# 03_External_Storage_Interface.net
KiCad netlist of a schematic drawn in Altium Designer
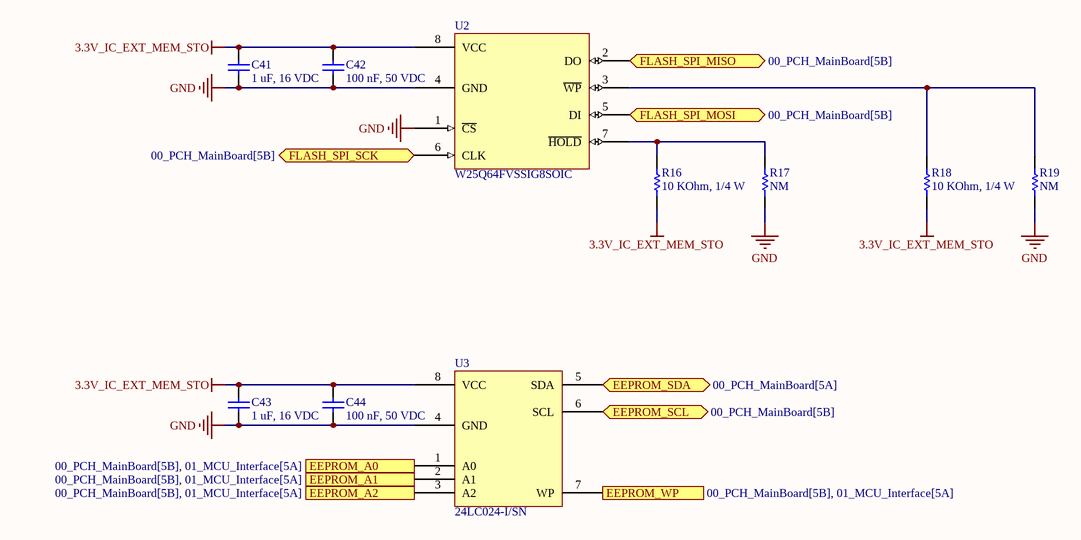
[diagram p0: 03_External_Storage_Interface.SchDoc]

(export (version "E")
  (design (tool "Eeschema 10.0.6"))
  (components
    (comp (ref "C41")
      (value "1 uF, 16 VDC")
      (footprint "CAP_0603")
      (description "CAP, size 0603, 1 uF, 16 VDC")
      (fields (field (name "TOLERANCE") "+/-10%"))
      (libsource (lib "Altium_Ceramic_Cap") (part "0106031051016"))
    )
    (comp (ref "C42")
      (value "100 nF, 50 VDC")
      (footprint "CAP_0603")
      (description "CAP, size 0603, 100 nF, 50 VDC")
      (fields (field (name "TOLERANCE") "+/-10%"))
      (libsource (lib "Altium_Ceramic_Cap") (part "0106031041050"))
    )
    (comp (ref "C43")
      (value "1 uF, 16 VDC")
      (footprint "CAP_0603")
      (description "CAP, size 0603, 1 uF, 16 VDC")
      (fields (field (name "TOLERANCE") "+/-10%"))
      (libsource (lib "Altium_Ceramic_Cap") (part "0106031051016"))
    )
    (comp (ref "C44")
      (value "100 nF, 50 VDC")
      (footprint "CAP_0603")
      (description "CAP, size 0603, 100 nF, 50 VDC")
      (fields (field (name "TOLERANCE") "+/-10%"))
      (libsource (lib "Altium_Ceramic_Cap") (part "0106031041050"))
    )
    (comp (ref "R16")
      (value "10 KOhm, 1/4 W")
      (footprint "resistor_0603")
      (description "RES, size 0603, 10 KOhm, 1/4 W")
      (libsource (lib "Altium_Resistor") (part "0006031031"))
    )
    (comp (ref "R17")
      (value "NM")
      (footprint "resistor_0603")
      (description "RES, size 0603, NM")
      (libsource (lib "Altium_Resistor") (part "000603_NM"))
    )
    (comp (ref "R18")
      (value "10 KOhm, 1/4 W")
      (footprint "resistor_0603")
      (description "RES, size 0603, 10 KOhm, 1/4 W")
      (libsource (lib "Altium_Resistor") (part "0006031031"))
    )
    (comp (ref "R19")
      (value "NM")
      (footprint "resistor_0603")
      (description "RES, size 0603, NM")
      (libsource (lib "Altium_Resistor") (part "000603_NM"))
    )
    (comp (ref "U2")
      (value "W25Q64FVSSIG8SOIC")
      (footprint "W25Qxx8SOIC")
      (description "IC FLASH 64MBIT SPI/QUAD 8SOIC")
      (fields (field (name "MANUFACTURER") "Winbond Electronics"))
      (libsource (lib "Altium_IC") (part "W25Q64FVSSIG8SOIC"))
    )
    (comp (ref "U3")
      (value "24LC024-I/SN")
      (footprint "24LCxxx-I/SN")
      (description "2 Kbit Electrically Erasable PROM")
      (fields (field (name "MANUFACTURER") "Microchip"))
      (libsource (lib "Altium_IC") (part "24LC024-I/SN"))
    )
  )
  (nets
    (net (code "1") (name "/EEPROM_A0") (class "Default")
      (node (ref "U3") (pin "1") (pinfunction "A0_1") (pintype "passive"))
    )
    (net (code "2") (name "/EEPROM_A1") (class "Default")
      (node (ref "U3") (pin "2") (pinfunction "A1_2") (pintype "passive"))
    )
    (net (code "3") (name "/EEPROM_A2") (class "Default")
      (node (ref "U3") (pin "3") (pinfunction "A2_3") (pintype "passive"))
    )
    (net (code "4") (name "/EEPROM_SCL") (class "Default")
      (node (ref "U3") (pin "6") (pinfunction "SCL_6") (pintype "passive"))
    )
    (net (code "5") (name "/EEPROM_SDA") (class "Default")
      (node (ref "U3") (pin "5") (pinfunction "SDA_5") (pintype "passive"))
    )
    (net (code "6") (name "/EEPROM_WP") (class "Default")
      (node (ref "U3") (pin "7") (pinfunction "WP_7") (pintype "passive"))
    )
    (net (code "7") (name "/FLASH_SPI_MISO") (class "Default")
      (node (ref "U2") (pin "2") (pinfunction "DO_2") (pintype "bidirectional"))
    )
    (net (code "8") (name "/FLASH_SPI_MOSI") (class "Default")
      (node (ref "U2") (pin "5") (pinfunction "DI_5") (pintype "bidirectional"))
    )
    (net (code "9") (name "/FLASH_SPI_SCK") (class "Default")
      (node (ref "U2") (pin "6") (pinfunction "CLK_6") (pintype "input"))
    )
    (net (code "10") (name "3.3V_IC_EXT_MEM_STO") (class "Default")
      (node (ref "C41") (pin "2") (pinfunction "2_2") (pintype "passive"))
      (node (ref "C42") (pin "2") (pinfunction "2_2") (pintype "passive"))
      (node (ref "C43") (pin "2") (pinfunction "2_2") (pintype "passive"))
      (node (ref "C44") (pin "2") (pinfunction "2_2") (pintype "passive"))
      (node (ref "R16") (pin "1") (pinfunction "1_1") (pintype "passive"))
      (node (ref "R18") (pin "1") (pinfunction "1_1") (pintype "passive"))
      (node (ref "U2") (pin "8") (pinfunction "VCC_8") (pintype "power_in"))
      (node (ref "U3") (pin "8") (pinfunction "VCC_8") (pintype "passive"))
    )
    (net (code "11") (name "GND") (class "Default")
      (node (ref "C41") (pin "1") (pinfunction "1_1") (pintype "passive"))
      (node (ref "C42") (pin "1") (pinfunction "1_1") (pintype "passive"))
      (node (ref "C43") (pin "1") (pinfunction "1_1") (pintype "passive"))
      (node (ref "C44") (pin "1") (pinfunction "1_1") (pintype "passive"))
      (node (ref "R17") (pin "1") (pinfunction "1_1") (pintype "passive"))
      (node (ref "R19") (pin "1") (pinfunction "1_1") (pintype "passive"))
      (node (ref "U2") (pin "1") (pinfunction "~{CS}_1") (pintype "input"))
      (node (ref "U2") (pin "4") (pinfunction "GND_4") (pintype "power_in"))
      (node (ref "U3") (pin "4") (pinfunction "GND_4") (pintype "passive"))
    )
    (net (code "12") (name "Net-(U2-~{HOLD})") (class "Default")
      (node (ref "R16") (pin "2") (pinfunction "2_2") (pintype "passive"))
      (node (ref "R17") (pin "2") (pinfunction "2_2") (pintype "passive"))
      (node (ref "U2") (pin "7") (pinfunction "~{HOLD}_7") (pintype "bidirectional"))
    )
    (net (code "13") (name "Net-(U2-~{WP})") (class "Default")
      (node (ref "R18") (pin "2") (pinfunction "2_2") (pintype "passive"))
      (node (ref "R19") (pin "2") (pinfunction "2_2") (pintype "passive"))
      (node (ref "U2") (pin "3") (pinfunction "~{WP}_3") (pintype "bidirectional"))
    )
  )
)
